# Sensori_Base.net
KiCad netlist of a schematic drawn in EAGLE
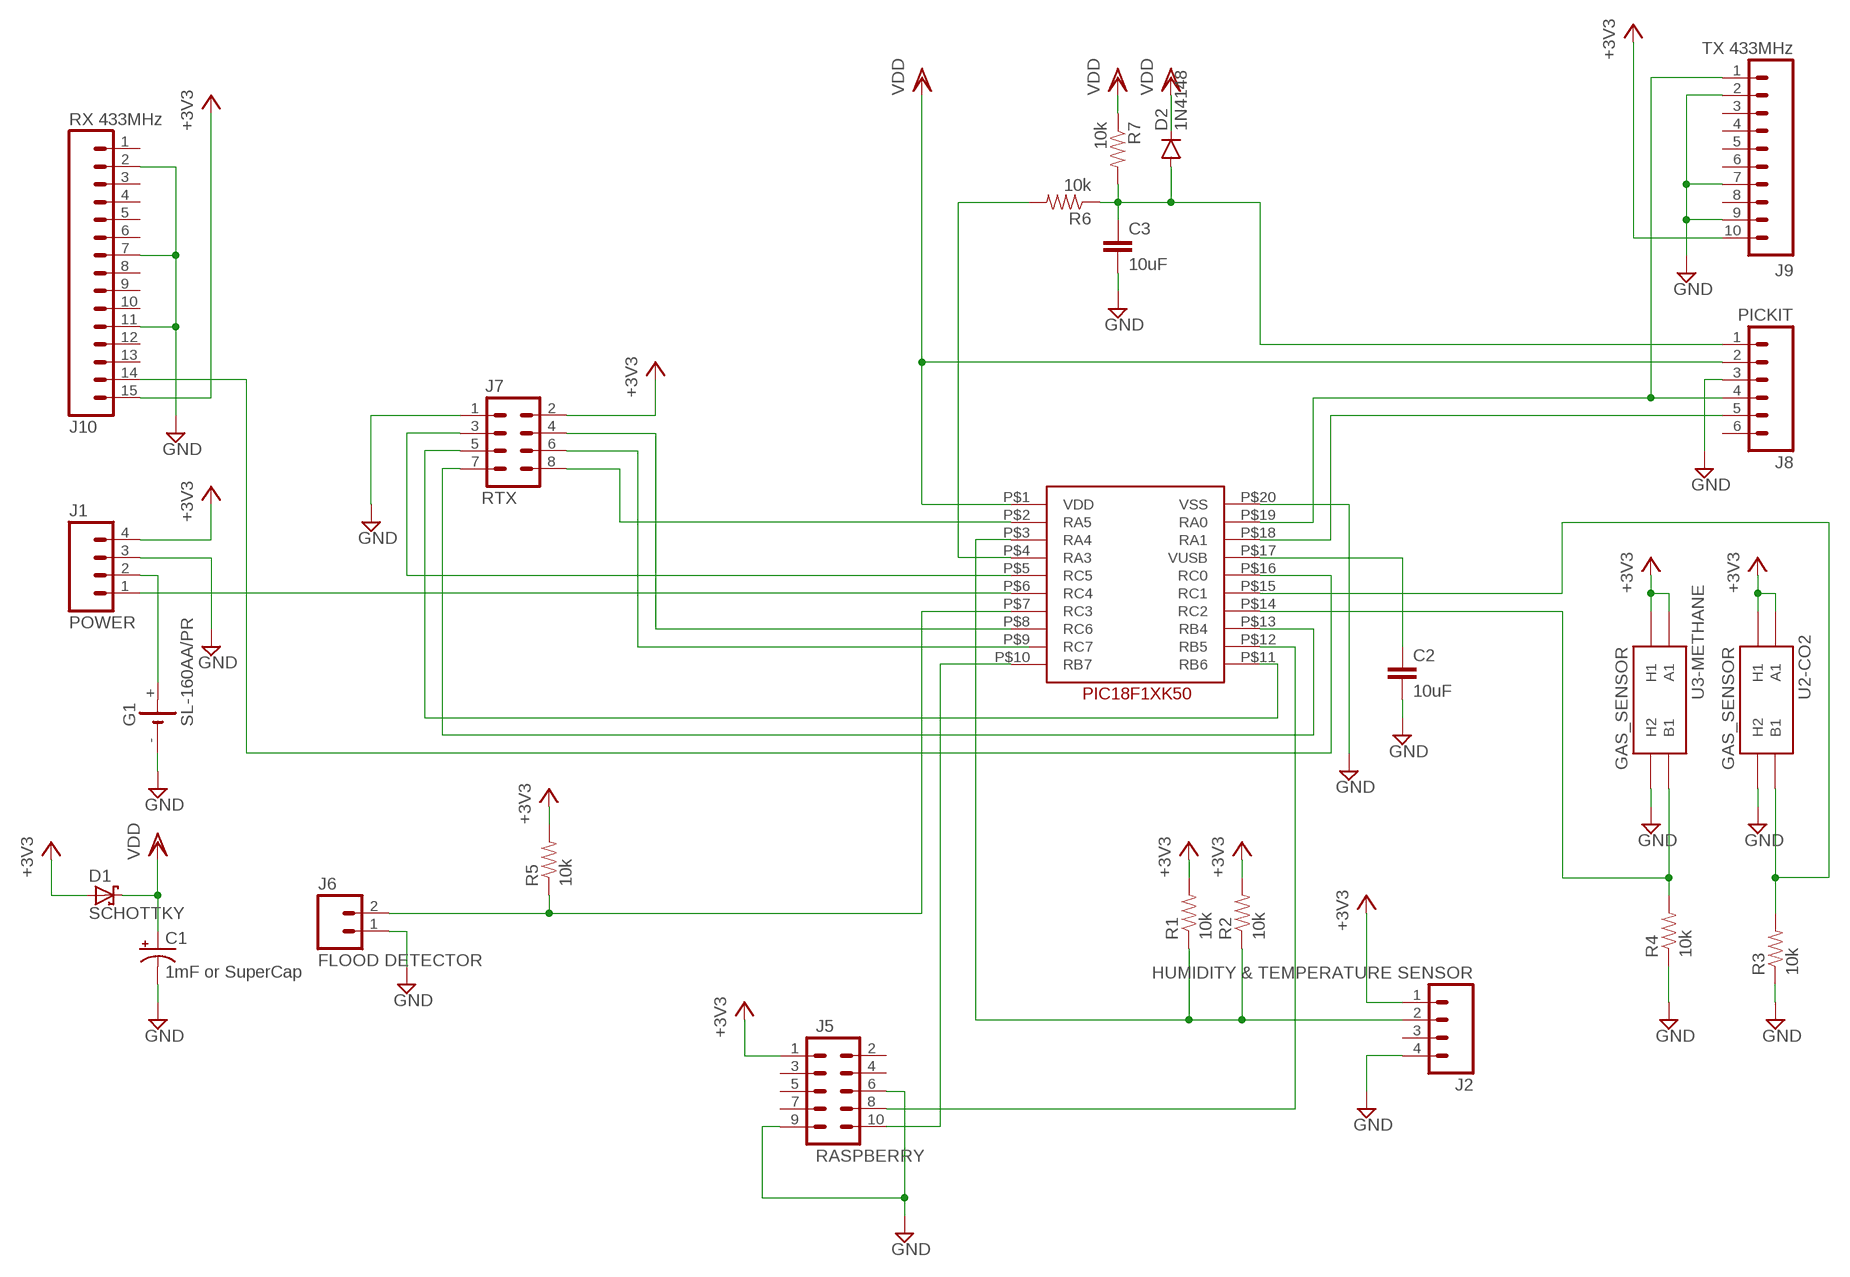
[diagram p0: schematic, sheet 1]

(export (version "E")
  (design (tool "Eeschema 10.0.6"))
  (components
    (comp (ref "C1")
      (value "1mF or SuperCap")
      (footprint "eagle-import:CPOL-RADIAL-1000UF-25V")
      (libsource (lib "eagle-import") (part "CAP_POLPTH4"))
    )
    (comp (ref "C2")
      (value "10uF")
      (footprint "eagle-import:0603-CAP")
      (libsource (lib "eagle-import") (part "10UF-6.3V-20%(0603)"))
    )
    (comp (ref "C3")
      (value "10uF")
      (footprint "eagle-import:0603-CAP")
      (libsource (lib "eagle-import") (part "10UF-6.3V-20%(0603)"))
    )
    (comp (ref "D1")
      (value "SCHOTTKY")
      (footprint "eagle-import:F126Z12")
      (libsource (lib "eagle-import") (part "SCHOTTKY-DIODEF126Z12"))
    )
    (comp (ref "D2")
      (value "1N4148")
      (footprint "eagle-import:DIODE-1N4148")
      (libsource (lib "eagle-import") (part "DIODE1N4148"))
    )
    (comp (ref "G1")
      (value "SL-160AA/PR")
      (footprint "eagle-import:SL-160AA_PR")
      (libsource (lib "eagle-import") (part "SL-160AA/PR"))
    )
    (comp (ref "J1")
      (value "POWER")
      (footprint "eagle-import:1X04_NO_SILK_ALL_ROUND")
      (libsource (lib "eagle-import") (part "M04NO_SILK_ALL_ROUND"))
    )
    (comp (ref "J2")
      (value "HUMIDITY & TEMPERATURE SENSOR")
      (footprint "eagle-import:1X04_NO_SILK_ALL_ROUND")
      (libsource (lib "eagle-import") (part "M04NO_SILK_ALL_ROUND"))
    )
    (comp (ref "J5")
      (value "RASPBERRY")
      (footprint "eagle-import:2X5_NOSILK")
      (libsource (lib "eagle-import") (part "M05X2NO_SILK"))
    )
    (comp (ref "J6")
      (value "FLOOD DETECTOR")
      (footprint "eagle-import:1X02_NO_SILK")
      (libsource (lib "eagle-import") (part "M021X02_NO_SILK"))
    )
    (comp (ref "J7")
      (value "RTX")
      (footprint "eagle-import:2X4")
      (libsource (lib "eagle-import") (part "M04X2"))
    )
    (comp (ref "J8")
      (value "PICKIT")
      (footprint "eagle-import:1X06_NO_SILK")
      (libsource (lib "eagle-import") (part "M06NO_SILK_FEMALE_PTH"))
    )
    (comp (ref "J9")
      (value "TX 433MHz")
      (footprint "eagle-import:1X10_NO_SILK")
      (libsource (lib "eagle-import") (part "M10NO_SILK_PTH_FEMALE"))
    )
    (comp (ref "J10")
      (value "RX 433MHz")
      (footprint "eagle-import:1X15")
      (libsource (lib "eagle-import") (part "M15"))
    )
    (comp (ref "R1")
      (value "10k")
      (footprint "eagle-import:AXIAL-0.3EZ")
      (libsource (lib "eagle-import") (part "RESISTOREZ"))
    )
    (comp (ref "R2")
      (value "10k")
      (footprint "eagle-import:AXIAL-0.3EZ")
      (libsource (lib "eagle-import") (part "RESISTOREZ"))
    )
    (comp (ref "R3")
      (value "10k")
      (footprint "eagle-import:AXIAL-0.3EZ")
      (libsource (lib "eagle-import") (part "RESISTOREZ"))
    )
    (comp (ref "R4")
      (value "10k")
      (footprint "eagle-import:AXIAL-0.3EZ")
      (libsource (lib "eagle-import") (part "RESISTOREZ"))
    )
    (comp (ref "R5")
      (value "10k")
      (footprint "eagle-import:AXIAL-0.3EZ")
      (libsource (lib "eagle-import") (part "RESISTOREZ"))
    )
    (comp (ref "R6")
      (value "10k")
      (footprint "eagle-import:AXIAL-0.3EZ")
      (libsource (lib "eagle-import") (part "RESISTOREZ"))
    )
    (comp (ref "R7")
      (value "10k")
      (footprint "eagle-import:AXIAL-0.3EZ")
      (libsource (lib "eagle-import") (part "RESISTOREZ"))
    )
    (comp (ref "U$1")
      (value "PIC18F1XK50")
      (footprint "eagle-import:SPDIP-20PIN")
      (libsource (lib "eagle-import") (part "PIC18F1XK50"))
    )
    (comp (ref "U2-CO2")
      (value "GAS_SENSOR")
      (footprint "eagle-import:MQ-3")
      (libsource (lib "eagle-import") (part "GAS_SENSOR"))
    )
    (comp (ref "U3-METHANE")
      (value "GAS_SENSOR")
      (footprint "eagle-import:MQ-3")
      (libsource (lib "eagle-import") (part "GAS_SENSOR"))
    )
  )
  (nets
    (net (code "1") (name "+3V3") (class "Default")
      (node (ref "D1") (pin "A") (pinfunction "A_A") (pintype "passive"))
      (node (ref "J1") (pin "4") (pinfunction "4_4") (pintype "passive"))
      (node (ref "J10") (pin "15") (pinfunction "15_15") (pintype "passive"))
      (node (ref "J2") (pin "1") (pinfunction "1_1") (pintype "passive"))
      (node (ref "J5") (pin "1") (pinfunction "1_1") (pintype "passive"))
      (node (ref "J7") (pin "2") (pinfunction "2_2") (pintype "passive"))
      (node (ref "J9") (pin "10") (pinfunction "10_10") (pintype "passive"))
      (node (ref "R1") (pin "P$2") (pinfunction "2_P$2") (pintype "passive"))
      (node (ref "R2") (pin "P$2") (pinfunction "2_P$2") (pintype "passive"))
      (node (ref "R5") (pin "P$2") (pinfunction "2_P$2") (pintype "passive"))
      (node (ref "U2-CO2") (pin "A1") (pinfunction "A1_A1") (pintype "bidirectional"))
      (node (ref "U2-CO2") (pin "HA") (pinfunction "H1_HA") (pintype "bidirectional"))
      (node (ref "U3-METHANE") (pin "A1") (pinfunction "A1_A1") (pintype "bidirectional"))
      (node (ref "U3-METHANE") (pin "HA") (pinfunction "H1_HA") (pintype "bidirectional"))
    )
    (net (code "2") (name "GND") (class "Default")
      (node (ref "C1") (pin "2") (pinfunction "-_2") (pintype "passive"))
      (node (ref "C2") (pin "2") (pinfunction "2_2") (pintype "passive"))
      (node (ref "C3") (pin "2") (pinfunction "2_2") (pintype "passive"))
      (node (ref "G1") (pin "-") (pinfunction "-_-") (pintype "passive"))
      (node (ref "J1") (pin "3") (pinfunction "3_3") (pintype "passive"))
      (node (ref "J10") (pin "11") (pinfunction "11_11") (pintype "passive"))
      (node (ref "J10") (pin "2") (pinfunction "2_2") (pintype "passive"))
      (node (ref "J10") (pin "7") (pinfunction "7_7") (pintype "passive"))
      (node (ref "J2") (pin "4") (pinfunction "4_4") (pintype "passive"))
      (node (ref "J5") (pin "6") (pinfunction "6_6") (pintype "passive"))
      (node (ref "J5") (pin "9") (pinfunction "9_9") (pintype "passive"))
      (node (ref "J6") (pin "1") (pinfunction "1_1") (pintype "passive"))
      (node (ref "J7") (pin "1") (pinfunction "1_1") (pintype "passive"))
      (node (ref "J8") (pin "3") (pinfunction "3_3") (pintype "passive"))
      (node (ref "J9") (pin "2") (pinfunction "2_2") (pintype "passive"))
      (node (ref "J9") (pin "7") (pinfunction "7_7") (pintype "passive"))
      (node (ref "J9") (pin "9") (pinfunction "9_9") (pintype "passive"))
      (node (ref "R3") (pin "P$1") (pinfunction "1_P$1") (pintype "passive"))
      (node (ref "R4") (pin "P$1") (pinfunction "1_P$1") (pintype "passive"))
      (node (ref "U$1") (pin "P$20") (pinfunction "VSS_P$20") (pintype "bidirectional"))
      (node (ref "U2-CO2") (pin "HB") (pinfunction "H2_HB") (pintype "bidirectional"))
      (node (ref "U3-METHANE") (pin "HB") (pinfunction "H2_HB") (pintype "bidirectional"))
    )
    (net (code "3") (name "Net-(G1-Pad+)") (class "Default")
      (node (ref "G1") (pin "+") (pinfunction "+_+") (pintype "passive"))
      (node (ref "J1") (pin "2") (pinfunction "2_2") (pintype "passive"))
    )
    (net (code "4") (name "Net-(R1-1)") (class "Default")
      (node (ref "J2") (pin "2") (pinfunction "2_2") (pintype "passive"))
      (node (ref "R1") (pin "P$1") (pinfunction "1_P$1") (pintype "passive"))
      (node (ref "R2") (pin "P$1") (pinfunction "1_P$1") (pintype "passive"))
      (node (ref "U$1") (pin "P$3") (pinfunction "RA4_P$3") (pintype "bidirectional"))
    )
    (net (code "5") (name "Net-(R3-2)") (class "Default")
      (node (ref "R3") (pin "P$2") (pinfunction "2_P$2") (pintype "passive"))
      (node (ref "U$1") (pin "P$15") (pinfunction "RC1_P$15") (pintype "bidirectional"))
      (node (ref "U2-CO2") (pin "B1") (pinfunction "B1_B1") (pintype "bidirectional"))
    )
    (net (code "6") (name "Net-(R4-2)") (class "Default")
      (node (ref "R4") (pin "P$2") (pinfunction "2_P$2") (pintype "passive"))
      (node (ref "U$1") (pin "P$14") (pinfunction "RC2_P$14") (pintype "bidirectional"))
      (node (ref "U3-METHANE") (pin "B1") (pinfunction "B1_B1") (pintype "bidirectional"))
    )
    (net (code "7") (name "Net-(R5-1)") (class "Default")
      (node (ref "J6") (pin "2") (pinfunction "2_2") (pintype "passive"))
      (node (ref "R5") (pin "P$1") (pinfunction "1_P$1") (pintype "passive"))
      (node (ref "U$1") (pin "P$7") (pinfunction "RC3_P$7") (pintype "bidirectional"))
    )
    (net (code "8") (name "Net-(R6-1)") (class "Default")
      (node (ref "C3") (pin "1") (pinfunction "1_1") (pintype "passive"))
      (node (ref "D2") (pin "A") (pinfunction "A_A") (pintype "passive"))
      (node (ref "J8") (pin "1") (pinfunction "1_1") (pintype "passive"))
      (node (ref "R6") (pin "P$1") (pinfunction "1_P$1") (pintype "passive"))
      (node (ref "R7") (pin "P$2") (pinfunction "2_P$2") (pintype "passive"))
    )
    (net (code "9") (name "Net-(R6-2)") (class "Default")
      (node (ref "R6") (pin "P$2") (pinfunction "2_P$2") (pintype "passive"))
      (node (ref "U$1") (pin "P$4") (pinfunction "RA3_P$4") (pintype "bidirectional"))
    )
    (net (code "10") (name "Net-(U$1-RA0)") (class "Default")
      (node (ref "J8") (pin "4") (pinfunction "4_4") (pintype "passive"))
      (node (ref "J9") (pin "1") (pinfunction "1_1") (pintype "passive"))
      (node (ref "U$1") (pin "P$19") (pinfunction "RA0_P$19") (pintype "bidirectional"))
    )
    (net (code "11") (name "Net-(U$1-RA1)") (class "Default")
      (node (ref "J8") (pin "5") (pinfunction "5_5") (pintype "passive"))
      (node (ref "U$1") (pin "P$18") (pinfunction "RA1_P$18") (pintype "bidirectional"))
    )
    (net (code "12") (name "Net-(U$1-RA5)") (class "Default")
      (node (ref "J7") (pin "8") (pinfunction "8_8") (pintype "passive"))
      (node (ref "U$1") (pin "P$2") (pinfunction "RA5_P$2") (pintype "bidirectional"))
    )
    (net (code "13") (name "Net-(U$1-RB4)") (class "Default")
      (node (ref "J7") (pin "7") (pinfunction "7_7") (pintype "passive"))
      (node (ref "U$1") (pin "P$13") (pinfunction "RB4_P$13") (pintype "bidirectional"))
    )
    (net (code "14") (name "Net-(U$1-RB5)") (class "Default")
      (node (ref "J5") (pin "8") (pinfunction "8_8") (pintype "passive"))
      (node (ref "U$1") (pin "P$12") (pinfunction "RB5_P$12") (pintype "bidirectional"))
    )
    (net (code "15") (name "Net-(U$1-RB6)") (class "Default")
      (node (ref "J7") (pin "5") (pinfunction "5_5") (pintype "passive"))
      (node (ref "U$1") (pin "P$11") (pinfunction "RB6_P$11") (pintype "bidirectional"))
    )
    (net (code "16") (name "Net-(U$1-RB7)") (class "Default")
      (node (ref "J5") (pin "10") (pinfunction "10_10") (pintype "passive"))
      (node (ref "U$1") (pin "P$10") (pinfunction "RB7_P$10") (pintype "bidirectional"))
    )
    (net (code "17") (name "Net-(U$1-RC0)") (class "Default")
      (node (ref "J10") (pin "14") (pinfunction "14_14") (pintype "passive"))
      (node (ref "U$1") (pin "P$16") (pinfunction "RC0_P$16") (pintype "bidirectional"))
    )
    (net (code "18") (name "Net-(U$1-RC4)") (class "Default")
      (node (ref "J1") (pin "1") (pinfunction "1_1") (pintype "passive"))
      (node (ref "U$1") (pin "P$6") (pinfunction "RC4_P$6") (pintype "bidirectional"))
    )
    (net (code "19") (name "Net-(U$1-RC5)") (class "Default")
      (node (ref "J7") (pin "3") (pinfunction "3_3") (pintype "passive"))
      (node (ref "U$1") (pin "P$5") (pinfunction "RC5_P$5") (pintype "bidirectional"))
    )
    (net (code "20") (name "Net-(U$1-RC6)") (class "Default")
      (node (ref "J7") (pin "4") (pinfunction "4_4") (pintype "passive"))
      (node (ref "U$1") (pin "P$8") (pinfunction "RC6_P$8") (pintype "bidirectional"))
    )
    (net (code "21") (name "Net-(U$1-VUSB)") (class "Default")
      (node (ref "C2") (pin "1") (pinfunction "1_1") (pintype "passive"))
      (node (ref "U$1") (pin "P$17") (pinfunction "VUSB_P$17") (pintype "bidirectional"))
    )
    (net (code "22") (name "VDD") (class "Default")
      (node (ref "C1") (pin "1") (pinfunction "+_1") (pintype "passive"))
      (node (ref "D1") (pin "C") (pinfunction "C_C") (pintype "passive"))
      (node (ref "D2") (pin "C") (pinfunction "C_C") (pintype "passive"))
      (node (ref "J8") (pin "2") (pinfunction "2_2") (pintype "passive"))
      (node (ref "R7") (pin "P$1") (pinfunction "1_P$1") (pintype "passive"))
      (node (ref "U$1") (pin "P$1") (pinfunction "VDD_P$1") (pintype "bidirectional"))
    )
    (net (code "23") (name "unconnected-(J2-Pad3)") (class "Default")
      (node (ref "J2") (pin "3") (pinfunction "3_3") (pintype "passive"))
    )
    (net (code "24") (name "unconnected-(J5-Pad2)") (class "Default")
      (node (ref "J5") (pin "2") (pinfunction "2_2") (pintype "passive"))
    )
    (net (code "25") (name "unconnected-(J5-Pad3)") (class "Default")
      (node (ref "J5") (pin "3") (pinfunction "3_3") (pintype "passive"))
    )
    (net (code "26") (name "unconnected-(J5-Pad4)") (class "Default")
      (node (ref "J5") (pin "4") (pinfunction "4_4") (pintype "passive"))
    )
    (net (code "27") (name "unconnected-(J5-Pad5)") (class "Default")
      (node (ref "J5") (pin "5") (pinfunction "5_5") (pintype "passive"))
    )
    (net (code "28") (name "unconnected-(J5-Pad7)") (class "Default")
      (node (ref "J5") (pin "7") (pinfunction "7_7") (pintype "passive"))
    )
    (net (code "29") (name "unconnected-(J7-Pad6)") (class "Default")
      (node (ref "J7") (pin "6") (pinfunction "6_6") (pintype "passive"))
    )
    (net (code "30") (name "unconnected-(J8-Pad6)") (class "Default")
      (node (ref "J8") (pin "6") (pinfunction "6_6") (pintype "passive"))
    )
    (net (code "31") (name "unconnected-(J9-Pad3)") (class "Default")
      (node (ref "J9") (pin "3") (pinfunction "3_3") (pintype "passive"))
    )
    (net (code "32") (name "unconnected-(J9-Pad4)") (class "Default")
      (node (ref "J9") (pin "4") (pinfunction "4_4") (pintype "passive"))
    )
    (net (code "33") (name "unconnected-(J9-Pad5)") (class "Default")
      (node (ref "J9") (pin "5") (pinfunction "5_5") (pintype "passive"))
    )
    (net (code "34") (name "unconnected-(J9-Pad6)") (class "Default")
      (node (ref "J9") (pin "6") (pinfunction "6_6") (pintype "passive"))
    )
    (net (code "35") (name "unconnected-(J9-Pad8)") (class "Default")
      (node (ref "J9") (pin "8") (pinfunction "8_8") (pintype "passive"))
    )
    (net (code "36") (name "unconnected-(J10-Pad1)") (class "Default")
      (node (ref "J10") (pin "1") (pinfunction "1_1") (pintype "passive"))
    )
    (net (code "37") (name "unconnected-(J10-Pad3)") (class "Default")
      (node (ref "J10") (pin "3") (pinfunction "3_3") (pintype "passive"))
    )
    (net (code "38") (name "unconnected-(J10-Pad4)") (class "Default")
      (node (ref "J10") (pin "4") (pinfunction "4_4") (pintype "passive"))
    )
    (net (code "39") (name "unconnected-(J10-Pad5)") (class "Default")
      (node (ref "J10") (pin "5") (pinfunction "5_5") (pintype "passive"))
    )
    (net (code "40") (name "unconnected-(J10-Pad6)") (class "Default")
      (node (ref "J10") (pin "6") (pinfunction "6_6") (pintype "passive"))
    )
    (net (code "41") (name "unconnected-(J10-Pad8)") (class "Default")
      (node (ref "J10") (pin "8") (pinfunction "8_8") (pintype "passive"))
    )
    (net (code "42") (name "unconnected-(J10-Pad9)") (class "Default")
      (node (ref "J10") (pin "9") (pinfunction "9_9") (pintype "passive"))
    )
    (net (code "43") (name "unconnected-(J10-Pad10)") (class "Default")
      (node (ref "J10") (pin "10") (pinfunction "10_10") (pintype "passive"))
    )
    (net (code "44") (name "unconnected-(J10-Pad12)") (class "Default")
      (node (ref "J10") (pin "12") (pinfunction "12_12") (pintype "passive"))
    )
    (net (code "45") (name "unconnected-(J10-Pad13)") (class "Default")
      (node (ref "J10") (pin "13") (pinfunction "13_13") (pintype "passive"))
    )
    (net (code "46") (name "unconnected-(U$1-RC7-PadP$9)") (class "Default")
      (node (ref "U$1") (pin "P$9") (pinfunction "RC7_P$9") (pintype "bidirectional"))
    )
  )
)
